# buck_converters_v1_1.net
KiCad netlist of a schematic drawn in EAGLE
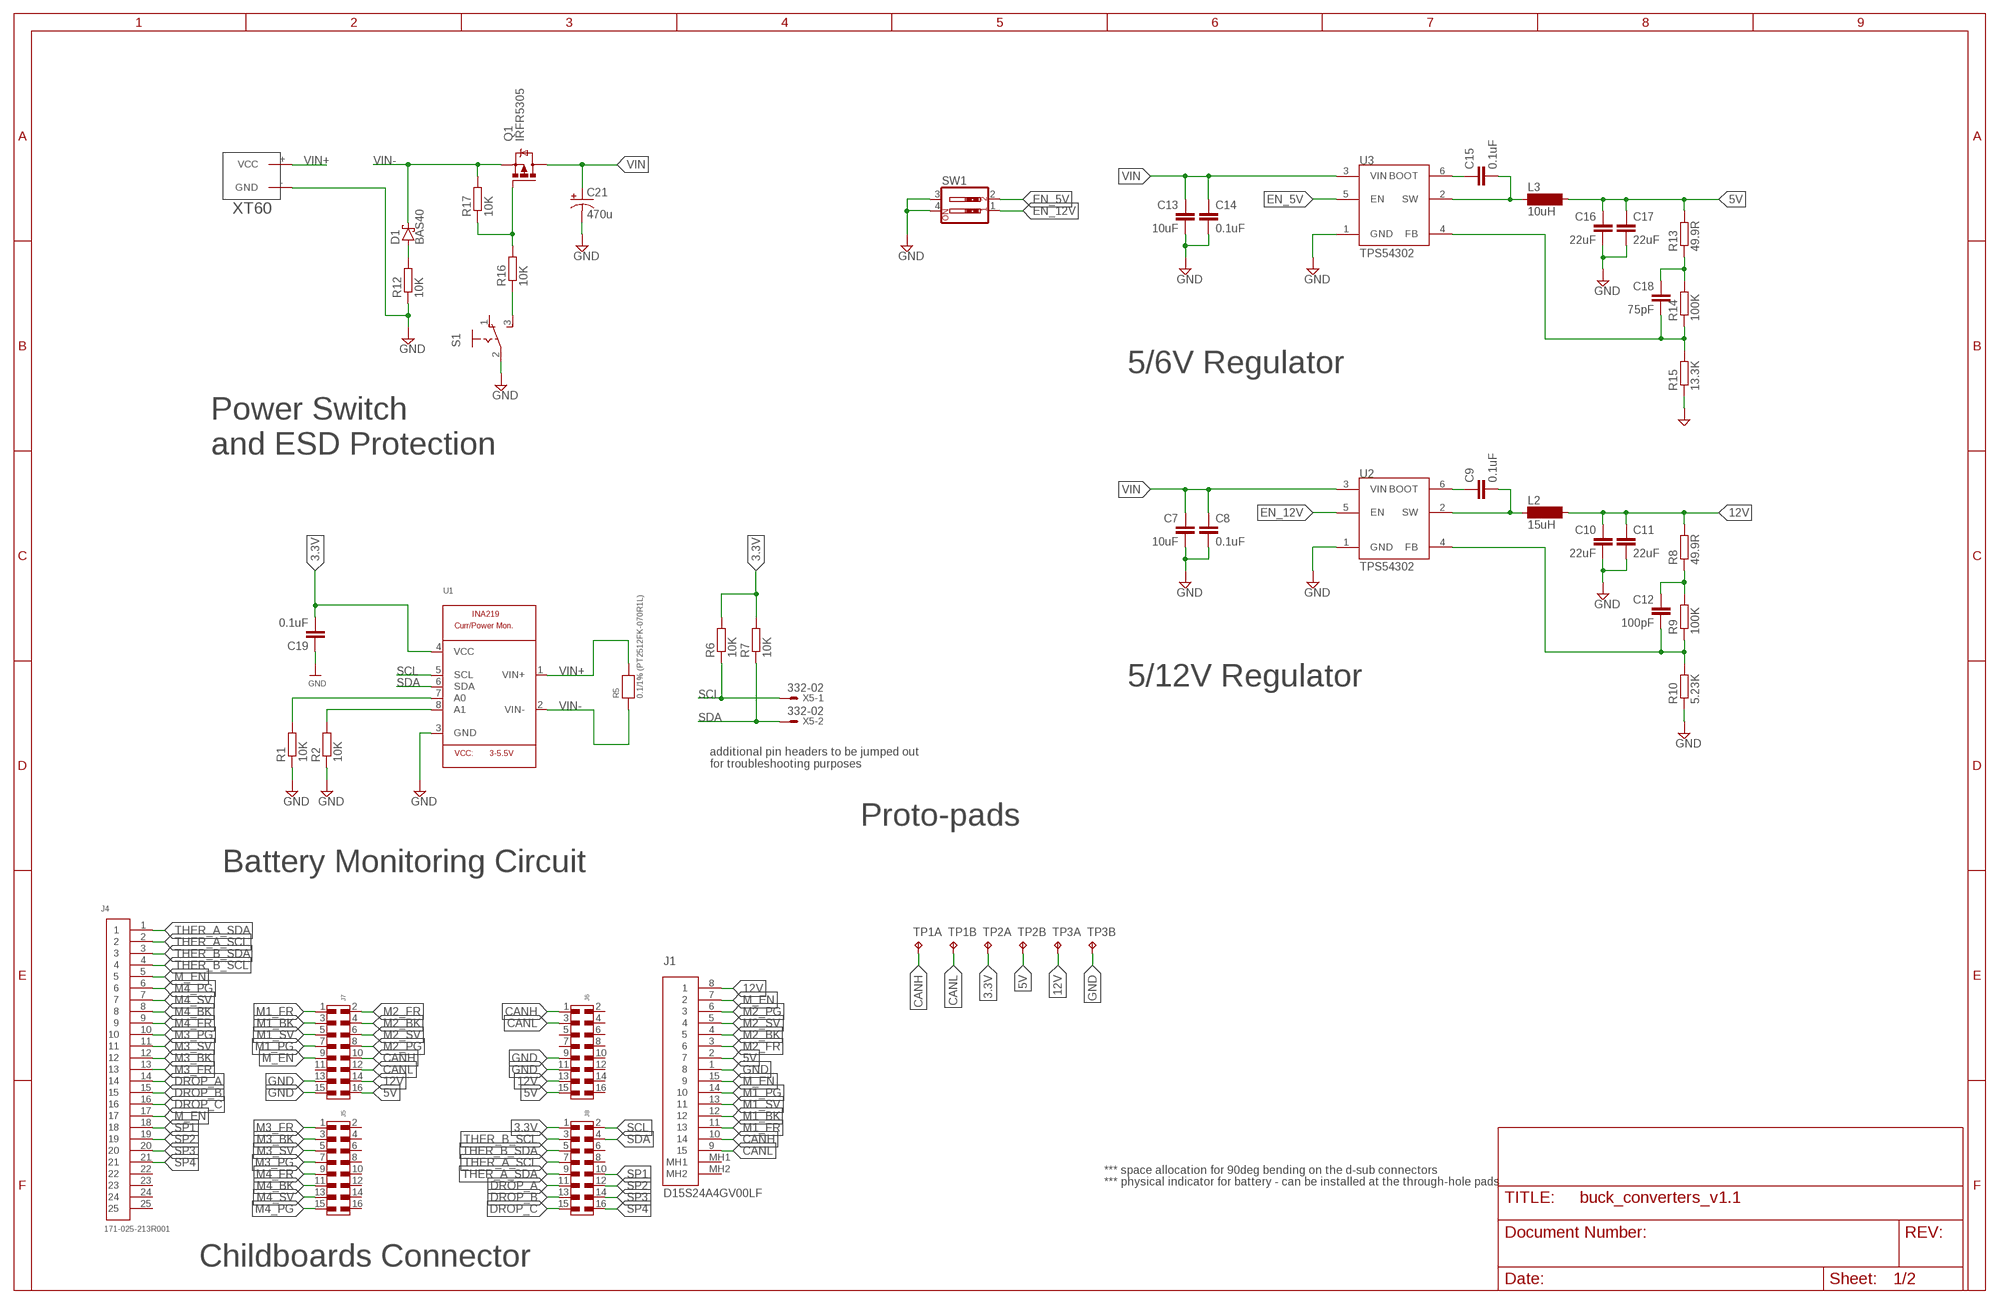
[diagram p0: schematic, sheet 1]
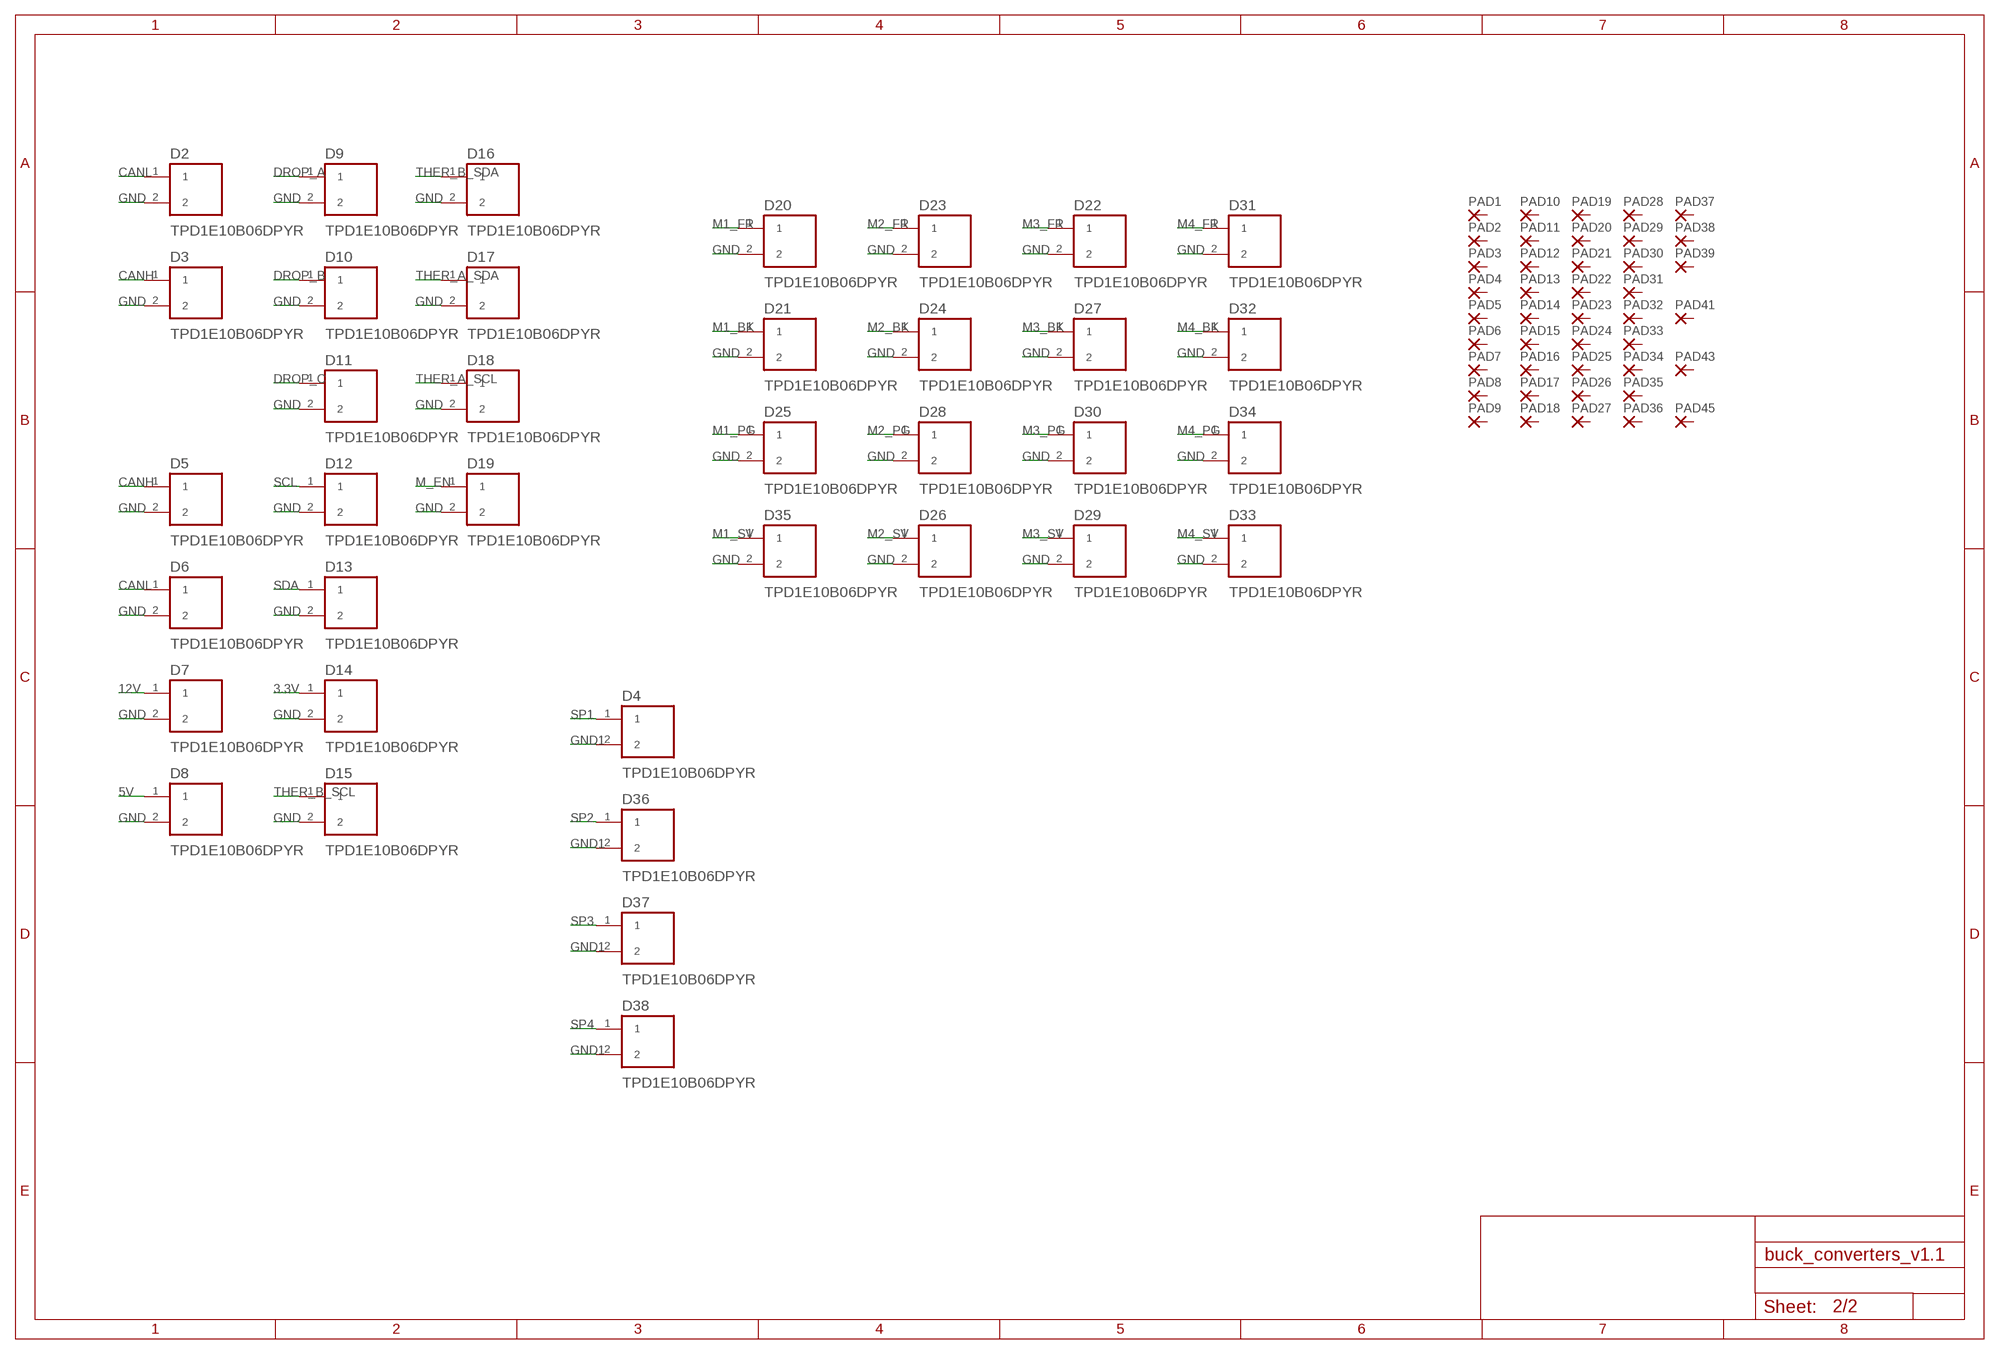
[diagram p1: schematic, sheet 2]

(export (version "E")
  (design (tool "Eeschema 10.0.6"))
  (components
    (comp (ref "C7")
      (value "10uF")
      (footprint "eagle-import:C0805")
      (libsource (lib "eagle-import") (part "C-EUC0805"))
    )
    (comp (ref "C8")
      (value "0.1uF")
      (footprint "eagle-import:C0805")
      (libsource (lib "eagle-import") (part "C-EUC0805"))
    )
    (comp (ref "C9")
      (value "0.1uF")
      (footprint "eagle-import:C0805")
      (libsource (lib "eagle-import") (part "C-EUC0805"))
    )
    (comp (ref "C10")
      (value "22uF")
      (footprint "eagle-import:C0805")
      (libsource (lib "eagle-import") (part "C-EUC0805"))
    )
    (comp (ref "C11")
      (value "22uF")
      (footprint "eagle-import:C0805")
      (libsource (lib "eagle-import") (part "C-EUC0805"))
    )
    (comp (ref "C12")
      (value "100pF")
      (footprint "eagle-import:C0805")
      (libsource (lib "eagle-import") (part "C-EUC0805"))
    )
    (comp (ref "C13")
      (value "10uF")
      (footprint "eagle-import:C0805")
      (libsource (lib "eagle-import") (part "C-EUC0805"))
    )
    (comp (ref "C14")
      (value "0.1uF")
      (footprint "eagle-import:C0805")
      (libsource (lib "eagle-import") (part "C-EUC0805"))
    )
    (comp (ref "C15")
      (value "0.1uF")
      (footprint "eagle-import:C0805")
      (libsource (lib "eagle-import") (part "C-EUC0805"))
    )
    (comp (ref "C16")
      (value "22uF")
      (footprint "eagle-import:C0805")
      (libsource (lib "eagle-import") (part "C-EUC0805"))
    )
    (comp (ref "C17")
      (value "22uF")
      (footprint "eagle-import:C0805")
      (libsource (lib "eagle-import") (part "C-EUC0805"))
    )
    (comp (ref "C18")
      (value "75pF")
      (footprint "eagle-import:C0805")
      (libsource (lib "eagle-import") (part "C-EUC0805"))
    )
    (comp (ref "C19")
      (value "0.1uF")
      (footprint "eagle-import:C0805")
      (libsource (lib "eagle-import") (part "C-EUC0805"))
    )
    (comp (ref "C21")
      (value "470u")
      (footprint "eagle-import:153CLV-1010")
      (libsource (lib "eagle-import") (part "CPOL-US153CLV-1010"))
    )
    (comp (ref "D1")
      (value "BAS40")
      (footprint "eagle-import:SOT23")
      (libsource (lib "eagle-import") (part "BAS40"))
    )
    (comp (ref "J1")
      (value "D15S24A4GV00LF")
      (footprint "eagle-import:D15S24A4GV00LF")
      (fields
        (field (name "DIGIKEY_PART_NUMBER") "609-1497-ND")
        (field (name "MANUFACTURER") "Amphenol ICC (FCI)")
        (field (name "CREATED_BY") "PCBLayout.com")
      )
      (libsource (lib "eagle-import") (part "D15S24A4GV00LF"))
    )
    (comp (ref "J4")
      (value "171-025-213R001")
      (footprint "eagle-import:171-025-213R001")
      (fields
        (field (name "DIGIKEY_PART_NO") "4225FE-ND")
        (field (name "MANUFACTURER") "NorComp Inc.")
        (field (name "CREATED_BY") "PCBLayout.com")
      )
      (libsource (lib "eagle-import") (part "171-025-213R001"))
    )
    (comp (ref "J5")
      (value "6120XX20621_61201620621")
      (footprint "eagle-import:61201620621")
      (libsource (lib "eagle-import") (part "6120XX20621_61201620621"))
    )
    (comp (ref "J6")
      (value "6120XX20621_61201620621")
      (footprint "eagle-import:61201620621")
      (libsource (lib "eagle-import") (part "6120XX20621_61201620621"))
    )
    (comp (ref "J7")
      (value "6123XX20621_61231620621")
      (footprint "eagle-import:61231620621")
      (libsource (lib "eagle-import") (part "6123XX20621_61231620621"))
    )
    (comp (ref "J8")
      (value "6120XX20621_61201620621")
      (footprint "eagle-import:61201620621")
      (libsource (lib "eagle-import") (part "6120XX20621_61201620621"))
    )
    (comp (ref "L2")
      (value "15uH")
      (footprint "eagle-import:SM-NE29")
      (libsource (lib "eagle-import") (part "SM-NE29"))
    )
    (comp (ref "L3")
      (value "10uH")
      (footprint "eagle-import:SM-NE29")
      (libsource (lib "eagle-import") (part "SM-NE29"))
    )
    (comp (ref "Q1")
      (value "IRFR5305")
      (footprint "eagle-import:D-PAK_TO252AA")
      (libsource (lib "eagle-import") (part "IRF?5305R"))
    )
    (comp (ref "R1")
      (value "10K")
      (footprint "eagle-import:R0805")
      (libsource (lib "eagle-import") (part "R-EU_R0805"))
    )
    (comp (ref "R2")
      (value "10K")
      (footprint "eagle-import:R0805")
      (libsource (lib "eagle-import") (part "R-EU_R0805"))
    )
    (comp (ref "R5")
      (value "0.1/1% (PT2512FK-070R1L)")
      (footprint "eagle-import:2512")
      (libsource (lib "eagle-import") (part "RESISTOR2512"))
    )
    (comp (ref "R6")
      (value "10K")
      (footprint "eagle-import:R0805")
      (libsource (lib "eagle-import") (part "R-EU_R0805"))
    )
    (comp (ref "R7")
      (value "10K")
      (footprint "eagle-import:R0805")
      (libsource (lib "eagle-import") (part "R-EU_R0805"))
    )
    (comp (ref "R8")
      (value "49.9R")
      (footprint "eagle-import:R0805")
      (libsource (lib "eagle-import") (part "R-EU_R0805"))
    )
    (comp (ref "R9")
      (value "100K")
      (footprint "eagle-import:R0805")
      (libsource (lib "eagle-import") (part "R-EU_R0805"))
    )
    (comp (ref "R10")
      (value "5.23K")
      (footprint "eagle-import:R0805")
      (libsource (lib "eagle-import") (part "R-EU_R0805"))
    )
    (comp (ref "R12")
      (value "10K")
      (footprint "eagle-import:R0805")
      (libsource (lib "eagle-import") (part "R-EU_R0805"))
    )
    (comp (ref "R13")
      (value "49.9R")
      (footprint "eagle-import:R0805")
      (libsource (lib "eagle-import") (part "R-EU_R0805"))
    )
    (comp (ref "R14")
      (value "100K")
      (footprint "eagle-import:R0805")
      (libsource (lib "eagle-import") (part "R-EU_R0805"))
    )
    (comp (ref "R15")
      (value "13.3K")
      (footprint "eagle-import:R0805")
      (libsource (lib "eagle-import") (part "R-EU_R0805"))
    )
    (comp (ref "R16")
      (value "10K")
      (footprint "eagle-import:R0805")
      (libsource (lib "eagle-import") (part "R-EU_R0805"))
    )
    (comp (ref "R17")
      (value "10K")
      (footprint "eagle-import:R0805")
      (libsource (lib "eagle-import") (part "R-EU_R0805"))
    )
    (comp (ref "S1")
      (value "255SB")
      (footprint "eagle-import:255SB")
      (libsource (lib "eagle-import") (part "255SB"))
    )
    (comp (ref "SW1")
      (value "SW_DIP-2")
      (footprint "eagle-import:EDG-02")
      (libsource (lib "eagle-import") (part "SW_DIP-2"))
    )
    (comp (ref "TP1")
      (value "TP2P2-38-17")
      (footprint "eagle-import:P2-38-17")
      (libsource (lib "eagle-import") (part "TP2P2-38-17"))
    )
    (comp (ref "TP2")
      (value "TP2P2-38-17")
      (footprint "eagle-import:P2-38-17")
      (libsource (lib "eagle-import") (part "TP2P2-38-17"))
    )
    (comp (ref "TP3")
      (value "TP2P2-38-17")
      (footprint "eagle-import:P2-38-17")
      (libsource (lib "eagle-import") (part "TP2P2-38-17"))
    )
    (comp (ref "U$9")
      (value "XT60")
      (footprint "eagle-import:XT60")
      (libsource (lib "eagle-import") (part "XT60"))
    )
    (comp (ref "U1")
      (value "INA219")
      (footprint "eagle-import:SOT23-8")
      (libsource (lib "eagle-import") (part "INA219"))
    )
    (comp (ref "U2")
      (value "TPS54302")
      (footprint "eagle-import:SOT23-6")
      (libsource (lib "eagle-import") (part "TPS54302"))
    )
    (comp (ref "U3")
      (value "TPS54302")
      (footprint "eagle-import:SOT23-6")
      (libsource (lib "eagle-import") (part "TPS54302"))
    )
    (comp (ref "X5")
      (value "332-02")
      (footprint "eagle-import:332-02")
      (libsource (lib "eagle-import") (part "332-02"))
    )
    (comp (ref "D2")
      (value "TPD1E10B06DPYR")
      (footprint "eagle-import:DIO_TPD1E05U06DPYR")
      (fields (field (name "MF") "Texas Instruments"))
      (libsource (lib "eagle-import") (part "TPD1E10B06DPYR"))
    )
    (comp (ref "D3")
      (value "TPD1E10B06DPYR")
      (footprint "eagle-import:DIO_TPD1E05U06DPYR")
      (fields (field (name "MF") "Texas Instruments"))
      (libsource (lib "eagle-import") (part "TPD1E10B06DPYR"))
    )
    (comp (ref "D4")
      (value "TPD1E10B06DPYR")
      (footprint "eagle-import:DIO_TPD1E05U06DPYR")
      (fields (field (name "MF") "Texas Instruments"))
      (libsource (lib "eagle-import") (part "TPD1E10B06DPYR"))
    )
    (comp (ref "D5")
      (value "TPD1E10B06DPYR")
      (footprint "eagle-import:DIO_TPD1E05U06DPYR")
      (fields (field (name "MF") "Texas Instruments"))
      (libsource (lib "eagle-import") (part "TPD1E10B06DPYR"))
    )
    (comp (ref "D6")
      (value "TPD1E10B06DPYR")
      (footprint "eagle-import:DIO_TPD1E05U06DPYR")
      (fields (field (name "MF") "Texas Instruments"))
      (libsource (lib "eagle-import") (part "TPD1E10B06DPYR"))
    )
    (comp (ref "D7")
      (value "TPD1E10B06DPYR")
      (footprint "eagle-import:DIO_TPD1E05U06DPYR")
      (fields (field (name "MF") "Texas Instruments"))
      (libsource (lib "eagle-import") (part "TPD1E10B06DPYR"))
    )
    (comp (ref "D8")
      (value "TPD1E10B06DPYR")
      (footprint "eagle-import:DIO_TPD1E05U06DPYR")
      (fields (field (name "MF") "Texas Instruments"))
      (libsource (lib "eagle-import") (part "TPD1E10B06DPYR"))
    )
    (comp (ref "D9")
      (value "TPD1E10B06DPYR")
      (footprint "eagle-import:DIO_TPD1E05U06DPYR")
      (fields (field (name "MF") "Texas Instruments"))
      (libsource (lib "eagle-import") (part "TPD1E10B06DPYR"))
    )
    (comp (ref "D10")
      (value "TPD1E10B06DPYR")
      (footprint "eagle-import:DIO_TPD1E05U06DPYR")
      (fields (field (name "MF") "Texas Instruments"))
      (libsource (lib "eagle-import") (part "TPD1E10B06DPYR"))
    )
    (comp (ref "D11")
      (value "TPD1E10B06DPYR")
      (footprint "eagle-import:DIO_TPD1E05U06DPYR")
      (fields (field (name "MF") "Texas Instruments"))
      (libsource (lib "eagle-import") (part "TPD1E10B06DPYR"))
    )
    (comp (ref "D12")
      (value "TPD1E10B06DPYR")
      (footprint "eagle-import:DIO_TPD1E05U06DPYR")
      (fields (field (name "MF") "Texas Instruments"))
      (libsource (lib "eagle-import") (part "TPD1E10B06DPYR"))
    )
    (comp (ref "D13")
      (value "TPD1E10B06DPYR")
      (footprint "eagle-import:DIO_TPD1E05U06DPYR")
      (fields (field (name "MF") "Texas Instruments"))
      (libsource (lib "eagle-import") (part "TPD1E10B06DPYR"))
    )
    (comp (ref "D14")
      (value "TPD1E10B06DPYR")
      (footprint "eagle-import:DIO_TPD1E05U06DPYR")
      (fields (field (name "MF") "Texas Instruments"))
      (libsource (lib "eagle-import") (part "TPD1E10B06DPYR"))
    )
    (comp (ref "D15")
      (value "TPD1E10B06DPYR")
      (footprint "eagle-import:DIO_TPD1E05U06DPYR")
      (fields (field (name "MF") "Texas Instruments"))
      (libsource (lib "eagle-import") (part "TPD1E10B06DPYR"))
    )
    (comp (ref "D16")
      (value "TPD1E10B06DPYR")
      (footprint "eagle-import:DIO_TPD1E05U06DPYR")
      (fields (field (name "MF") "Texas Instruments"))
      (libsource (lib "eagle-import") (part "TPD1E10B06DPYR"))
    )
    (comp (ref "D17")
      (value "TPD1E10B06DPYR")
      (footprint "eagle-import:DIO_TPD1E05U06DPYR")
      (fields (field (name "MF") "Texas Instruments"))
      (libsource (lib "eagle-import") (part "TPD1E10B06DPYR"))
    )
    (comp (ref "D18")
      (value "TPD1E10B06DPYR")
      (footprint "eagle-import:DIO_TPD1E05U06DPYR")
      (fields (field (name "MF") "Texas Instruments"))
      (libsource (lib "eagle-import") (part "TPD1E10B06DPYR"))
    )
    (comp (ref "D19")
      (value "TPD1E10B06DPYR")
      (footprint "eagle-import:DIO_TPD1E05U06DPYR")
      (fields (field (name "MF") "Texas Instruments"))
      (libsource (lib "eagle-import") (part "TPD1E10B06DPYR"))
    )
    (comp (ref "D20")
      (value "TPD1E10B06DPYR")
      (footprint "eagle-import:DIO_TPD1E05U06DPYR")
      (fields (field (name "MF") "Texas Instruments"))
      (libsource (lib "eagle-import") (part "TPD1E10B06DPYR"))
    )
    (comp (ref "D21")
      (value "TPD1E10B06DPYR")
      (footprint "eagle-import:DIO_TPD1E05U06DPYR")
      (fields (field (name "MF") "Texas Instruments"))
      (libsource (lib "eagle-import") (part "TPD1E10B06DPYR"))
    )
    (comp (ref "D22")
      (value "TPD1E10B06DPYR")
      (footprint "eagle-import:DIO_TPD1E05U06DPYR")
      (fields (field (name "MF") "Texas Instruments"))
      (libsource (lib "eagle-import") (part "TPD1E10B06DPYR"))
    )
    (comp (ref "D23")
      (value "TPD1E10B06DPYR")
      (footprint "eagle-import:DIO_TPD1E05U06DPYR")
      (fields (field (name "MF") "Texas Instruments"))
      (libsource (lib "eagle-import") (part "TPD1E10B06DPYR"))
    )
    (comp (ref "D24")
      (value "TPD1E10B06DPYR")
      (footprint "eagle-import:DIO_TPD1E05U06DPYR")
      (fields (field (name "MF") "Texas Instruments"))
      (libsource (lib "eagle-import") (part "TPD1E10B06DPYR"))
    )
    (comp (ref "D25")
      (value "TPD1E10B06DPYR")
      (footprint "eagle-import:DIO_TPD1E05U06DPYR")
      (fields (field (name "MF") "Texas Instruments"))
      (libsource (lib "eagle-import") (part "TPD1E10B06DPYR"))
    )
    (comp (ref "D26")
      (value "TPD1E10B06DPYR")
      (footprint "eagle-import:DIO_TPD1E05U06DPYR")
      (fields (field (name "MF") "Texas Instruments"))
      (libsource (lib "eagle-import") (part "TPD1E10B06DPYR"))
    )
    (comp (ref "D27")
      (value "TPD1E10B06DPYR")
      (footprint "eagle-import:DIO_TPD1E05U06DPYR")
      (fields (field (name "MF") "Texas Instruments"))
      (libsource (lib "eagle-import") (part "TPD1E10B06DPYR"))
    )
    (comp (ref "D28")
      (value "TPD1E10B06DPYR")
      (footprint "eagle-import:DIO_TPD1E05U06DPYR")
      (fields (field (name "MF") "Texas Instruments"))
      (libsource (lib "eagle-import") (part "TPD1E10B06DPYR"))
    )
    (comp (ref "D29")
      (value "TPD1E10B06DPYR")
      (footprint "eagle-import:DIO_TPD1E05U06DPYR")
      (fields (field (name "MF") "Texas Instruments"))
      (libsource (lib "eagle-import") (part "TPD1E10B06DPYR"))
    )
    (comp (ref "D30")
      (value "TPD1E10B06DPYR")
      (footprint "eagle-import:DIO_TPD1E05U06DPYR")
      (fields (field (name "MF") "Texas Instruments"))
      (libsource (lib "eagle-import") (part "TPD1E10B06DPYR"))
    )
    (comp (ref "D31")
      (value "TPD1E10B06DPYR")
      (footprint "eagle-import:DIO_TPD1E05U06DPYR")
      (fields (field (name "MF") "Texas Instruments"))
      (libsource (lib "eagle-import") (part "TPD1E10B06DPYR"))
    )
    (comp (ref "D32")
      (value "TPD1E10B06DPYR")
      (footprint "eagle-import:DIO_TPD1E05U06DPYR")
      (fields (field (name "MF") "Texas Instruments"))
      (libsource (lib "eagle-import") (part "TPD1E10B06DPYR"))
    )
    (comp (ref "D33")
      (value "TPD1E10B06DPYR")
      (footprint "eagle-import:DIO_TPD1E05U06DPYR")
      (fields (field (name "MF") "Texas Instruments"))
      (libsource (lib "eagle-import") (part "TPD1E10B06DPYR"))
    )
    (comp (ref "D34")
      (value "TPD1E10B06DPYR")
      (footprint "eagle-import:DIO_TPD1E05U06DPYR")
      (fields (field (name "MF") "Texas Instruments"))
      (libsource (lib "eagle-import") (part "TPD1E10B06DPYR"))
    )
    (comp (ref "D35")
      (value "TPD1E10B06DPYR")
      (footprint "eagle-import:DIO_TPD1E05U06DPYR")
      (fields (field (name "MF") "Texas Instruments"))
      (libsource (lib "eagle-import") (part "TPD1E10B06DPYR"))
    )
    (comp (ref "D36")
      (value "TPD1E10B06DPYR")
      (footprint "eagle-import:DIO_TPD1E05U06DPYR")
      (fields (field (name "MF") "Texas Instruments"))
      (libsource (lib "eagle-import") (part "TPD1E10B06DPYR"))
    )
    (comp (ref "D37")
      (value "TPD1E10B06DPYR")
      (footprint "eagle-import:DIO_TPD1E05U06DPYR")
      (fields (field (name "MF") "Texas Instruments"))
      (libsource (lib "eagle-import") (part "TPD1E10B06DPYR"))
    )
    (comp (ref "D38")
      (value "TPD1E10B06DPYR")
      (footprint "eagle-import:DIO_TPD1E05U06DPYR")
      (fields (field (name "MF") "Texas Instruments"))
      (libsource (lib "eagle-import") (part "TPD1E10B06DPYR"))
    )
    (comp (ref "PAD1")
      (value "2,54/1,1")
      (footprint "eagle-import:2,54_1,1")
      (libsource (lib "eagle-import") (part "2,54/1,1"))
    )
    (comp (ref "PAD2")
      (value "2,54/1,1")
      (footprint "eagle-import:2,54_1,1")
      (libsource (lib "eagle-import") (part "2,54/1,1"))
    )
    (comp (ref "PAD3")
      (value "2,54/1,1")
      (footprint "eagle-import:2,54_1,1")
      (libsource (lib "eagle-import") (part "2,54/1,1"))
    )
    (comp (ref "PAD4")
      (value "2,54/1,1")
      (footprint "eagle-import:2,54_1,1")
      (libsource (lib "eagle-import") (part "2,54/1,1"))
    )
    (comp (ref "PAD5")
      (value "2,54/1,1")
      (footprint "eagle-import:2,54_1,1")
      (libsource (lib "eagle-import") (part "2,54/1,1"))
    )
    (comp (ref "PAD6")
      (value "2,54/1,1")
      (footprint "eagle-import:2,54_1,1")
      (libsource (lib "eagle-import") (part "2,54/1,1"))
    )
    (comp (ref "PAD7")
      (value "2,54/1,1")
      (footprint "eagle-import:2,54_1,1")
      (libsource (lib "eagle-import") (part "2,54/1,1"))
    )
    (comp (ref "PAD8")
      (value "2,54/1,1")
      (footprint "eagle-import:2,54_1,1")
      (libsource (lib "eagle-import") (part "2,54/1,1"))
    )
    (comp (ref "PAD9")
      (value "2,54/1,1")
      (footprint "eagle-import:2,54_1,1")
      (libsource (lib "eagle-import") (part "2,54/1,1"))
    )
    (comp (ref "PAD10")
      (value "2,54/1,1")
      (footprint "eagle-import:2,54_1,1")
      (libsource (lib "eagle-import") (part "2,54/1,1"))
    )
    (comp (ref "PAD11")
      (value "2,54/1,1")
      (footprint "eagle-import:2,54_1,1")
      (libsource (lib "eagle-import") (part "2,54/1,1"))
    )
    (comp (ref "PAD12")
      (value "2,54/1,1")
      (footprint "eagle-import:2,54_1,1")
      (libsource (lib "eagle-import") (part "2,54/1,1"))
    )
    (comp (ref "PAD13")
      (value "2,54/1,1")
      (footprint "eagle-import:2,54_1,1")
      (libsource (lib "eagle-import") (part "2,54/1,1"))
    )
    (comp (ref "PAD14")
      (value "2,54/1,1")
      (footprint "eagle-import:2,54_1,1")
      (libsource (lib "eagle-import") (part "2,54/1,1"))
    )
    (comp (ref "PAD15")
      (value "2,54/1,1")
      (footprint "eagle-import:2,54_1,1")
      (libsource (lib "eagle-import") (part "2,54/1,1"))
    )
    (comp (ref "PAD16")
      (value "2,54/1,1")
      (footprint "eagle-import:2,54_1,1")
      (libsource (lib "eagle-import") (part "2,54/1,1"))
    )
    (comp (ref "PAD17")
      (value "2,54/1,1")
      (footprint "eagle-import:2,54_1,1")
      (libsource (lib "eagle-import") (part "2,54/1,1"))
    )
    (comp (ref "PAD18")
      (value "2,54/1,1")
      (footprint "eagle-import:2,54_1,1")
      (libsource (lib "eagle-import") (part "2,54/1,1"))
    )
    (comp (ref "PAD19")
      (value "2,54/1,1")
      (footprint "eagle-import:2,54_1,1")
      (libsource (lib "eagle-import") (part "2,54/1,1"))
    )
    (comp (ref "PAD20")
      (value "2,54/1,1")
      (footprint "eagle-import:2,54_1,1")
      (libsource (lib "eagle-import") (part "2,54/1,1"))
    )
    (comp (ref "PAD21")
      (value "2,54/1,1")
      (footprint "eagle-import:2,54_1,1")
      (libsource (lib "eagle-import") (part "2,54/1,1"))
    )
    (comp (ref "PAD22")
      (value "2,54/1,1")
      (footprint "eagle-import:2,54_1,1")
      (libsource (lib "eagle-import") (part "2,54/1,1"))
    )
    (comp (ref "PAD23")
      (value "2,54/1,1")
      (footprint "eagle-import:2,54_1,1")
      (libsource (lib "eagle-import") (part "2,54/1,1"))
    )
    (comp (ref "PAD24")
      (value "2,54/1,1")
      (footprint "eagle-import:2,54_1,1")
      (libsource (lib "eagle-import") (part "2,54/1,1"))
    )
    (comp (ref "PAD25")
      (value "2,54/1,1")
      (footprint "eagle-import:2,54_1,1")
      (libsource (lib "eagle-import") (part "2,54/1,1"))
    )
    (comp (ref "PAD26")
      (value "2,54/1,1")
      (footprint "eagle-import:2,54_1,1")
      (libsource (lib "eagle-import") (part "2,54/1,1"))
    )
    (comp (ref "PAD27")
      (value "2,54/1,1")
      (footprint "eagle-import:2,54_1,1")
      (libsource (lib "eagle-import") (part "2,54/1,1"))
    )
    (comp (ref "PAD28")
      (value "2,54/1,1")
      (footprint "eagle-import:2,54_1,1")
      (libsource (lib "eagle-import") (part "2,54/1,1"))
    )
    (comp (ref "PAD29")
      (value "2,54/1,1")
      (footprint "eagle-import:2,54_1,1")
      (libsource (lib "eagle-import") (part "2,54/1,1"))
    )
    (comp (ref "PAD30")
      (value "2,54/1,1")
      (footprint "eagle-import:2,54_1,1")
      (libsource (lib "eagle-import") (part "2,54/1,1"))
    )
    (comp (ref "PAD31")
      (value "2,54/1,1")
      (footprint "eagle-import:2,54_1,1")
      (libsource (lib "eagle-import") (part "2,54/1,1"))
    )
    (comp (ref "PAD32")
      (value "2,54/1,1")
      (footprint "eagle-import:2,54_1,1")
      (libsource (lib "eagle-import") (part "2,54/1,1"))
    )
    (comp (ref "PAD33")
      (value "2,54/1,1")
      (footprint "eagle-import:2,54_1,1")
      (libsource (lib "eagle-import") (part "2,54/1,1"))
    )
    (comp (ref "PAD34")
      (value "2,54/1,1")
      (footprint "eagle-import:2,54_1,1")
      (libsource (lib "eagle-import") (part "2,54/1,1"))
    )
    (comp (ref "PAD35")
      (value "2,54/1,1")
      (footprint "eagle-import:2,54_1,1")
      (libsource (lib "eagle-import") (part "2,54/1,1"))
    )
    (comp (ref "PAD36")
      (value "2,54/1,1")
      (footprint "eagle-import:2,54_1,1")
      (libsource (lib "eagle-import") (part "2,54/1,1"))
    )
    (comp (ref "PAD37")
      (value "2,54/1,1")
      (footprint "eagle-import:2,54_1,1")
      (libsource (lib "eagle-import") (part "2,54/1,1"))
    )
    (comp (ref "PAD38")
      (value "2,54/1,1")
      (footprint "eagle-import:2,54_1,1")
      (libsource (lib "eagle-import") (part "2,54/1,1"))
    )
    (comp (ref "PAD39")
      (value "2,54/1,1")
      (footprint "eagle-import:2,54_1,1")
      (libsource (lib "eagle-import") (part "2,54/1,1"))
    )
    (comp (ref "PAD41")
      (value "2,54/1,1")
      (footprint "eagle-import:2,54_1,1")
      (libsource (lib "eagle-import") (part "2,54/1,1"))
    )
    (comp (ref "PAD43")
      (value "2,54/1,1")
      (footprint "eagle-import:2,54_1,1")
      (libsource (lib "eagle-import") (part "2,54/1,1"))
    )
    (comp (ref "PAD45")
      (value "2,54/1,1")
      (footprint "eagle-import:2,54_1,1")
      (libsource (lib "eagle-import") (part "2,54/1,1"))
    )
  )
  (nets
    (net (code "1") (name "3.3V") (class "Default")
      (node (ref "C19") (pin "2") (pinfunction "2_2") (pintype "passive"))
      (node (ref "D14") (pin "1") (pinfunction "1_1") (pintype "bidirectional"))
      (node (ref "J8") (pin "1") (pinfunction "1_1") (pintype "passive"))
      (node (ref "R6") (pin "2") (pinfunction "2_2") (pintype "passive"))
      (node (ref "R7") (pin "2") (pinfunction "2_2") (pintype "passive"))
      (node (ref "TP2") (pin "TP-1") (pinfunction "TP_TP-1") (pintype "input"))
      (node (ref "U1") (pin "4") (pinfunction "VCC_4") (pintype "bidirectional"))
    )
    (net (code "2") (name "5V") (class "Default")
      (node (ref "C16") (pin "1") (pinfunction "1_1") (pintype "passive"))
      (node (ref "C17") (pin "1") (pinfunction "1_1") (pintype "passive"))
      (node (ref "D8") (pin "1") (pinfunction "1_1") (pintype "bidirectional"))
      (node (ref "J1") (pin "2") (pinfunction "7_2") (pintype "passive"))
      (node (ref "J6") (pin "15") (pinfunction "15_15") (pintype "passive"))
      (node (ref "J7") (pin "16") (pinfunction "16_16") (pintype "passive"))
      (node (ref "L3") (pin "2") (pinfunction "2_2") (pintype "passive"))
      (node (ref "R13") (pin "2") (pinfunction "2_2") (pintype "passive"))
      (node (ref "TP2") (pin "TP-2") (pinfunction "TP_TP-2") (pintype "input"))
    )
    (net (code "3") (name "12V") (class "Default")
      (node (ref "C10") (pin "1") (pinfunction "1_1") (pintype "passive"))
      (node (ref "C11") (pin "1") (pinfunction "1_1") (pintype "passive"))
      (node (ref "D7") (pin "1") (pinfunction "1_1") (pintype "bidirectional"))
      (node (ref "J1") (pin "8") (pinfunction "1_8") (pintype "passive"))
      (node (ref "J6") (pin "13") (pinfunction "13_13") (pintype "passive"))
      (node (ref "J7") (pin "14") (pinfunction "14_14") (pintype "passive"))
      (node (ref "L2") (pin "2") (pinfunction "2_2") (pintype "passive"))
      (node (ref "R8") (pin "2") (pinfunction "2_2") (pintype "passive"))
      (node (ref "TP3") (pin "TP-1") (pinfunction "TP_TP-1") (pintype "input"))
    )
    (net (code "4") (name "CANH") (class "Default")
      (node (ref "D3") (pin "1") (pinfunction "1_1") (pintype "bidirectional"))
      (node (ref "D5") (pin "1") (pinfunction "1_1") (pintype "bidirectional"))
      (node (ref "J1") (pin "10") (pinfunction "14_10") (pintype "passive"))
      (node (ref "J6") (pin "1") (pinfunction "1_1") (pintype "passive"))
      (node (ref "J7") (pin "10") (pinfunction "10_10") (pintype "passive"))
      (node (ref "TP1") (pin "TP-1") (pinfunction "TP_TP-1") (pintype "input"))
    )
    (net (code "5") (name "CANL") (class "Default")
      (node (ref "D2") (pin "1") (pinfunction "1_1") (pintype "bidirectional"))
      (node (ref "D6") (pin "1") (pinfunction "1_1") (pintype "bidirectional"))
      (node (ref "J1") (pin "9") (pinfunction "15_9") (pintype "passive"))
      (node (ref "J6") (pin "3") (pinfunction "3_3") (pintype "passive"))
      (node (ref "J7") (pin "12") (pinfunction "12_12") (pintype "passive"))
      (node (ref "TP1") (pin "TP-2") (pinfunction "TP_TP-2") (pintype "input"))
    )
    (net (code "6") (name "DROP_A") (class "Default")
      (node (ref "D9") (pin "1") (pinfunction "1_1") (pintype "bidirectional"))
      (node (ref "J4") (pin "14") (pinfunction "14_14") (pintype "passive"))
      (node (ref "J8") (pin "11") (pinfunction "11_11") (pintype "passive"))
    )
    (net (code "7") (name "DROP_B") (class "Default")
      (node (ref "D10") (pin "1") (pinfunction "1_1") (pintype "bidirectional"))
      (node (ref "J4") (pin "15") (pinfunction "15_15") (pintype "passive"))
      (node (ref "J8") (pin "13") (pinfunction "13_13") (pintype "passive"))
    )
    (net (code "8") (name "DROP_C") (class "Default")
      (node (ref "D11") (pin "1") (pinfunction "1_1") (pintype "bidirectional"))
      (node (ref "J4") (pin "16") (pinfunction "16_16") (pintype "passive"))
      (node (ref "J8") (pin "15") (pinfunction "15_15") (pintype "passive"))
    )
    (net (code "9") (name "EN_5V") (class "Default")
      (node (ref "SW1") (pin "2") (pinfunction "2_2") (pintype "passive"))
      (node (ref "U3") (pin "5") (pinfunction "EN_5") (pintype "bidirectional"))
    )
    (net (code "10") (name "EN_12V") (class "Default")
      (node (ref "SW1") (pin "1") (pinfunction "1_1") (pintype "passive"))
      (node (ref "U2") (pin "5") (pinfunction "EN_5") (pintype "bidirectional"))
    )
    (net (code "11") (name "GND") (class "Default")
      (node (ref "C10") (pin "2") (pinfunction "2_2") (pintype "passive"))
      (node (ref "C11") (pin "2") (pinfunction "2_2") (pintype "passive"))
      (node (ref "C13") (pin "2") (pinfunction "2_2") (pintype "passive"))
      (node (ref "C14") (pin "2") (pinfunction "2_2") (pintype "passive"))
      (node (ref "C16") (pin "2") (pinfunction "2_2") (pintype "passive"))
      (node (ref "C17") (pin "2") (pinfunction "2_2") (pintype "passive"))
      (node (ref "C19") (pin "1") (pinfunction "1_1") (pintype "passive"))
      (node (ref "C21") (pin "-") (pinfunction "-_-") (pintype "passive"))
      (node (ref "C7") (pin "2") (pinfunction "2_2") (pintype "passive"))
      (node (ref "C8") (pin "2") (pinfunction "2_2") (pintype "passive"))
      (node (ref "D10") (pin "2") (pinfunction "2_2") (pintype "bidirectional"))
      (node (ref "D11") (pin "2") (pinfunction "2_2") (pintype "bidirectional"))
      (node (ref "D12") (pin "2") (pinfunction "2_2") (pintype "bidirectional"))
      (node (ref "D13") (pin "2") (pinfunction "2_2") (pintype "bidirectional"))
      (node (ref "D14") (pin "2") (pinfunction "2_2") (pintype "bidirectional"))
      (node (ref "D15") (pin "2") (pinfunction "2_2") (pintype "bidirectional"))
      (node (ref "D16") (pin "2") (pinfunction "2_2") (pintype "bidirectional"))
      (node (ref "D17") (pin "2") (pinfunction "2_2") (pintype "bidirectional"))
      (node (ref "D18") (pin "2") (pinfunction "2_2") (pintype "bidirectional"))
      (node (ref "D19") (pin "2") (pinfunction "2_2") (pintype "bidirectional"))
      (node (ref "D2") (pin "2") (pinfunction "2_2") (pintype "bidirectional"))
      (node (ref "D20") (pin "2") (pinfunction "2_2") (pintype "bidirectional"))
      (node (ref "D21") (pin "2") (pinfunction "2_2") (pintype "bidirectional"))
      (node (ref "D22") (pin "2") (pinfunction "2_2") (pintype "bidirectional"))
      (node (ref "D23") (pin "2") (pinfunction "2_2") (pintype "bidirectional"))
      (node (ref "D24") (pin "2") (pinfunction "2_2") (pintype "bidirectional"))
      (node (ref "D25") (pin "2") (pinfunction "2_2") (pintype "bidirectional"))
      (node (ref "D26") (pin "2") (pinfunction "2_2") (pintype "bidirectional"))
      (node (ref "D27") (pin "2") (pinfunction "2_2") (pintype "bidirectional"))
      (node (ref "D28") (pin "2") (pinfunction "2_2") (pintype "bidirectional"))
      (node (ref "D29") (pin "2") (pinfunction "2_2") (pintype "bidirectional"))
      (node (ref "D3") (pin "2") (pinfunction "2_2") (pintype "bidirectional"))
      (node (ref "D30") (pin "2") (pinfunction "2_2") (pintype "bidirectional"))
      (node (ref "D31") (pin "2") (pinfunction "2_2") (pintype "bidirectional"))
      (node (ref "D32") (pin "2") (pinfunction "2_2") (pintype "bidirectional"))
      (node (ref "D33") (pin "2") (pinfunction "2_2") (pintype "bidirectional"))
      (node (ref "D34") (pin "2") (pinfunction "2_2") (pintype "bidirectional"))
      (node (ref "D35") (pin "2") (pinfunction "2_2") (pintype "bidirectional"))
      (node (ref "D5") (pin "2") (pinfunction "2_2") (pintype "bidirectional"))
      (node (ref "D6") (pin "2") (pinfunction "2_2") (pintype "bidirectional"))
      (node (ref "D7") (pin "2") (pinfunction "2_2") (pintype "bidirectional"))
      (node (ref "D8") (pin "2") (pinfunction "2_2") (pintype "bidirectional"))
      (node (ref "D9") (pin "2") (pinfunction "2_2") (pintype "bidirectional"))
      (node (ref "J1") (pin "1") (pinfunction "8_1") (pintype "passive"))
      (node (ref "J6") (pin "11") (pinfunction "11_11") (pintype "passive"))
      (node (ref "J6") (pin "9") (pinfunction "9_9") (pintype "passive"))
      (node (ref "J7") (pin "13") (pinfunction "13_13") (pintype "passive"))
      (node (ref "J7") (pin "15") (pinfunction "15_15") (pintype "passive"))
      (node (ref "R1") (pin "1") (pinfunction "1_1") (pintype "passive"))
      (node (ref "R10") (pin "1") (pinfunction "1_1") (pintype "passive"))
      (node (ref "R12") (pin "1") (pinfunction "1_1") (pintype "passive"))
      (node (ref "R15") (pin "1") (pinfunction "1_1") (pintype "passive"))
      (node (ref "R2") (pin "1") (pinfunction "1_1") (pintype "passive"))
      (node (ref "S1") (pin "2") (pinfunction "P_2") (pintype "passive"))
      (node (ref "SW1") (pin "3") (pinfunction "3_3") (pintype "passive"))
      (node (ref "SW1") (pin "4") (pinfunction "4_4") (pintype "passive"))
      (node (ref "TP3") (pin "TP-2") (pinfunction "TP_TP-2") (pintype "input"))
      (node (ref "U$9") (pin "-") (pinfunction "GND_-") (pintype "bidirectional"))
      (node (ref "U1") (pin "3") (pinfunction "GND_3") (pintype "bidirectional"))
      (node (ref "U2") (pin "1") (pinfunction "GND_1") (pintype "bidirectional"))
      (node (ref "U3") (pin "1") (pinfunction "GND_1") (pintype "bidirectional"))
    )
    (net (code "12") (name "GND1") (class "Default")
      (node (ref "D36") (pin "2") (pinfunction "2_2") (pintype "bidirectional"))
      (node (ref "D37") (pin "2") (pinfunction "2_2") (pintype "bidirectional"))
      (node (ref "D38") (pin "2") (pinfunction "2_2") (pintype "bidirectional"))
      (node (ref "D4") (pin "2") (pinfunction "2_2") (pintype "bidirectional"))
    )
    (net (code "13") (name "M1_BK") (class "Default")
      (node (ref "D21") (pin "1") (pinfunction "1_1") (pintype "bidirectional"))
      (node (ref "J1") (pin "12") (pinfunction "12_12") (pintype "passive"))
      (node (ref "J7") (pin "3") (pinfunction "3_3") (pintype "passive"))
    )
    (net (code "14") (name "M1_FR") (class "Default")
      (node (ref "D20") (pin "1") (pinfunction "1_1") (pintype "bidirectional"))
      (node (ref "J1") (pin "11") (pinfunction "13_11") (pintype "passive"))
      (node (ref "J7") (pin "1") (pinfunction "1_1") (pintype "passive"))
    )
    (net (code "15") (name "M1_PG") (class "Default")
      (node (ref "D25") (pin "1") (pinfunction "1_1") (pintype "bidirectional"))
      (node (ref "J1") (pin "14") (pinfunction "10_14") (pintype "passive"))
      (node (ref "J7") (pin "7") (pinfunction "7_7") (pintype "passive"))
    )
    (net (code "16") (name "M1_SV") (class "Default")
      (node (ref "D35") (pin "1") (pinfunction "1_1") (pintype "bidirectional"))
      (node (ref "J1") (pin "13") (pinfunction "11_13") (pintype "passive"))
      (node (ref "J7") (pin "5") (pinfunction "5_5") (pintype "passive"))
    )
    (net (code "17") (name "M2_BK") (class "Default")
      (node (ref "D24") (pin "1") (pinfunction "1_1") (pintype "bidirectional"))
      (node (ref "J1") (pin "4") (pinfunction "5_4") (pintype "passive"))
      (node (ref "J7") (pin "4") (pinfunction "4_4") (pintype "passive"))
    )
    (net (code "18") (name "M2_FR") (class "Default")
      (node (ref "D23") (pin "1") (pinfunction "1_1") (pintype "bidirectional"))
      (node (ref "J1") (pin "3") (pinfunction "6_3") (pintype "passive"))
      (node (ref "J7") (pin "2") (pinfunction "2_2") (pintype "passive"))
    )
    (net (code "19") (name "M2_PG") (class "Default")
      (node (ref "D28") (pin "1") (pinfunction "1_1") (pintype "bidirectional"))
      (node (ref "J1") (pin "6") (pinfunction "3_6") (pintype "passive"))
      (node (ref "J7") (pin "8") (pinfunction "8_8") (pintype "passive"))
    )
    (net (code "20") (name "M2_SV") (class "Default")
      (node (ref "D26") (pin "1") (pinfunction "1_1") (pintype "bidirectional"))
      (node (ref "J1") (pin "5") (pinfunction "4_5") (pintype "passive"))
      (node (ref "J7") (pin "6") (pinfunction "6_6") (pintype "passive"))
    )
    (net (code "21") (name "M3_BK") (class "Default")
      (node (ref "D27") (pin "1") (pinfunction "1_1") (pintype "bidirectional"))
      (node (ref "J4") (pin "12") (pinfunction "12_12") (pintype "passive"))
      (node (ref "J5") (pin "3") (pinfunction "3_3") (pintype "passive"))
    )
    (net (code "22") (name "M3_FR") (class "Default")
      (node (ref "D22") (pin "1") (pinfunction "1_1") (pintype "bidirectional"))
      (node (ref "J4") (pin "13") (pinfunction "13_13") (pintype "passive"))
      (node (ref "J5") (pin "1") (pinfunction "1_1") (pintype "passive"))
    )
    (net (code "23") (name "M3_PG") (class "Default")
      (node (ref "D30") (pin "1") (pinfunction "1_1") (pintype "bidirectional"))
      (node (ref "J4") (pin "10") (pinfunction "10_10") (pintype "passive"))
      (node (ref "J5") (pin "7") (pinfunction "7_7") (pintype "passive"))
    )
    (net (code "24") (name "M3_SV") (class "Default")
      (node (ref "D29") (pin "1") (pinfunction "1_1") (pintype "bidirectional"))
      (node (ref "J4") (pin "11") (pinfunction "11_11") (pintype "passive"))
      (node (ref "J5") (pin "5") (pinfunction "5_5") (pintype "passive"))
    )
    (net (code "25") (name "M4_BK") (class "Default")
      (node (ref "D32") (pin "1") (pinfunction "1_1") (pintype "bidirectional"))
      (node (ref "J4") (pin "8") (pinfunction "8_8") (pintype "passive"))
      (node (ref "J5") (pin "11") (pinfunction "11_11") (pintype "passive"))
    )
    (net (code "26") (name "M4_FR") (class "Default")
      (node (ref "D31") (pin "1") (pinfunction "1_1") (pintype "bidirectional"))
      (node (ref "J4") (pin "9") (pinfunction "9_9") (pintype "passive"))
      (node (ref "J5") (pin "9") (pinfunction "9_9") (pintype "passive"))
    )
    (net (code "27") (name "M4_PG") (class "Default")
      (node (ref "D34") (pin "1") (pinfunction "1_1") (pintype "bidirectional"))
      (node (ref "J4") (pin "6") (pinfunction "6_6") (pintype "passive"))
      (node (ref "J5") (pin "15") (pinfunction "15_15") (pintype "passive"))
    )
    (net (code "28") (name "M4_SV") (class "Default")
      (node (ref "D33") (pin "1") (pinfunction "1_1") (pintype "bidirectional"))
      (node (ref "J4") (pin "7") (pinfunction "7_7") (pintype "passive"))
      (node (ref "J5") (pin "13") (pinfunction "13_13") (pintype "passive"))
    )
    (net (code "29") (name "M_EN") (class "Default")
      (node (ref "D19") (pin "1") (pinfunction "1_1") (pintype "bidirectional"))
      (node (ref "J1") (pin "15") (pinfunction "9_15") (pintype "passive"))
      (node (ref "J1") (pin "7") (pinfunction "2_7") (pintype "passive"))
      (node (ref "J4") (pin "17") (pinfunction "17_17") (pintype "passive"))
      (node (ref "J4") (pin "5") (pinfunction "5_5") (pintype "passive"))
      (node (ref "J7") (pin "9") (pinfunction "9_9") (pintype "passive"))
    )
    (net (code "30") (name "Net-(C12-Pad1)") (class "Default")
      (node (ref "C12") (pin "1") (pinfunction "1_1") (pintype "passive"))
      (node (ref "R8") (pin "1") (pinfunction "1_1") (pintype "passive"))
      (node (ref "R9") (pin "2") (pinfunction "2_2") (pintype "passive"))
    )
    (net (code "31") (name "Net-(C18-Pad1)") (class "Default")
      (node (ref "C18") (pin "1") (pinfunction "1_1") (pintype "passive"))
      (node (ref "R13") (pin "1") (pinfunction "1_1") (pintype "passive"))
      (node (ref "R14") (pin "2") (pinfunction "2_2") (pintype "passive"))
    )
    (net (code "32") (name "Net-(D1-A)") (class "Default")
      (node (ref "D1") (pin "1") (pinfunction "A_1") (pintype "passive"))
      (node (ref "R12") (pin "2") (pinfunction "2_2") (pintype "passive"))
    )
    (net (code "33") (name "Net-(Q1-G)") (class "Default")
      (node (ref "Q1") (pin "1") (pinfunction "G_1") (pintype "passive"))
      (node (ref "R16") (pin "2") (pinfunction "2_2") (pintype "passive"))
      (node (ref "R17") (pin "1") (pinfunction "1_1") (pintype "passive"))
    )
    (net (code "34") (name "Net-(S1-S)") (class "Default")
      (node (ref "R16") (pin "1") (pinfunction "1_1") (pintype "passive"))
      (node (ref "S1") (pin "3") (pinfunction "S_3") (pintype "passive"))
    )
    (net (code "35") (name "Net-(U1-A0)") (class "Default")
      (node (ref "R1") (pin "2") (pinfunction "2_2") (pintype "passive"))
      (node (ref "U1") (pin "7") (pinfunction "A0_7") (pintype "bidirectional"))
    )
    (net (code "36") (name "Net-(U1-A1)") (class "Default")
      (node (ref "R2") (pin "2") (pinfunction "2_2") (pintype "passive"))
      (node (ref "U1") (pin "8") (pinfunction "A1_8") (pintype "bidirectional"))
    )
    (net (code "37") (name "Net-(U2-BOOT)") (class "Default")
      (node (ref "C9") (pin "1") (pinfunction "1_1") (pintype "passive"))
      (node (ref "U2") (pin "6") (pinfunction "BOOT_6") (pintype "bidirectional"))
    )
    (net (code "38") (name "Net-(U2-FB)") (class "Default")
      (node (ref "C12") (pin "2") (pinfunction "2_2") (pintype "passive"))
      (node (ref "R10") (pin "2") (pinfunction "2_2") (pintype "passive"))
      (node (ref "R9") (pin "1") (pinfunction "1_1") (pintype "passive"))
      (node (ref "U2") (pin "4") (pinfunction "FB_4") (pintype "bidirectional"))
    )
    (net (code "39") (name "Net-(U2-SW)") (class "Default")
      (node (ref "C9") (pin "2") (pinfunction "2_2") (pintype "passive"))
      (node (ref "L2") (pin "1") (pinfunction "1_1") (pintype "passive"))
      (node (ref "U2") (pin "2") (pinfunction "SW_2") (pintype "bidirectional"))
    )
    (net (code "40") (name "Net-(U3-BOOT)") (class "Default")
      (node (ref "C15") (pin "1") (pinfunction "1_1") (pintype "passive"))
      (node (ref "U3") (pin "6") (pinfunction "BOOT_6") (pintype "bidirectional"))
    )
    (net (code "41") (name "Net-(U3-FB)") (class "Default")
      (node (ref "C18") (pin "2") (pinfunction "2_2") (pintype "passive"))
      (node (ref "R14") (pin "1") (pinfunction "1_1") (pintype "passive"))
      (node (ref "R15") (pin "2") (pinfunction "2_2") (pintype "passive"))
      (node (ref "U3") (pin "4") (pinfunction "FB_4") (pintype "bidirectional"))
    )
    (net (code "42") (name "Net-(U3-SW)") (class "Default")
      (node (ref "C15") (pin "2") (pinfunction "2_2") (pintype "passive"))
      (node (ref "L3") (pin "1") (pinfunction "1_1") (pintype "passive"))
      (node (ref "U3") (pin "2") (pinfunction "SW_2") (pintype "bidirectional"))
    )
    (net (code "43") (name "SCL") (class "Default")
      (node (ref "D12") (pin "1") (pinfunction "1_1") (pintype "bidirectional"))
      (node (ref "J8") (pin "2") (pinfunction "2_2") (pintype "passive"))
      (node (ref "R6") (pin "1") (pinfunction "1_1") (pintype "passive"))
      (node (ref "U1") (pin "5") (pinfunction "SCL_5") (pintype "bidirectional"))
      (node (ref "X5") (pin "1") (pinfunction "S_1") (pintype "passive"))
    )
    (net (code "44") (name "SDA") (class "Default")
      (node (ref "D13") (pin "1") (pinfunction "1_1") (pintype "bidirectional"))
      (node (ref "J8") (pin "4") (pinfunction "4_4") (pintype "passive"))
      (node (ref "R7") (pin "1") (pinfunction "1_1") (pintype "passive"))
      (node (ref "U1") (pin "6") (pinfunction "SDA_6") (pintype "bidirectional"))
      (node (ref "X5") (pin "2") (pinfunction "S_2") (pintype "passive"))
    )
    (net (code "45") (name "SP1") (class "Default")
      (node (ref "D4") (pin "1") (pinfunction "1_1") (pintype "bidirectional"))
      (node (ref "J4") (pin "18") (pinfunction "18_18") (pintype "passive"))
      (node (ref "J8") (pin "10") (pinfunction "10_10") (pintype "passive"))
    )
    (net (code "46") (name "SP2") (class "Default")
      (node (ref "D36") (pin "1") (pinfunction "1_1") (pintype "bidirectional"))
      (node (ref "J4") (pin "19") (pinfunction "19_19") (pintype "passive"))
      (node (ref "J8") (pin "12") (pinfunction "12_12") (pintype "passive"))
    )
    (net (code "47") (name "SP3") (class "Default")
      (node (ref "D37") (pin "1") (pinfunction "1_1") (pintype "bidirectional"))
      (node (ref "J4") (pin "20") (pinfunction "20_20") (pintype "passive"))
      (node (ref "J8") (pin "14") (pinfunction "14_14") (pintype "passive"))
    )
    (net (code "48") (name "SP4") (class "Default")
      (node (ref "D38") (pin "1") (pinfunction "1_1") (pintype "bidirectional"))
      (node (ref "J4") (pin "21") (pinfunction "21_21") (pintype "passive"))
      (node (ref "J8") (pin "16") (pinfunction "16_16") (pintype "passive"))
    )
    (net (code "49") (name "THER_A_SCL") (class "Default")
      (node (ref "D18") (pin "1") (pinfunction "1_1") (pintype "bidirectional"))
      (node (ref "J4") (pin "2") (pinfunction "2_2") (pintype "passive"))
      (node (ref "J8") (pin "7") (pinfunction "7_7") (pintype "passive"))
    )
    (net (code "50") (name "THER_A_SDA") (class "Default")
      (node (ref "D17") (pin "1") (pinfunction "1_1") (pintype "bidirectional"))
      (node (ref "J4") (pin "1") (pinfunction "1_1") (pintype "passive"))
      (node (ref "J8") (pin "9") (pinfunction "9_9") (pintype "passive"))
    )
    (net (code "51") (name "THER_B_SCL") (class "Default")
      (node (ref "D15") (pin "1") (pinfunction "1_1") (pintype "bidirectional"))
      (node (ref "J4") (pin "4") (pinfunction "4_4") (pintype "passive"))
      (node (ref "J8") (pin "3") (pinfunction "3_3") (pintype "passive"))
    )
    (net (code "52") (name "THER_B_SDA") (class "Default")
      (node (ref "D16") (pin "1") (pinfunction "1_1") (pintype "bidirectional"))
      (node (ref "J4") (pin "3") (pinfunction "3_3") (pintype "passive"))
      (node (ref "J8") (pin "5") (pinfunction "5_5") (pintype "passive"))
    )
    (net (code "53") (name "VIN") (class "Default")
      (node (ref "C13") (pin "1") (pinfunction "1_1") (pintype "passive"))
      (node (ref "C14") (pin "1") (pinfunction "1_1") (pintype "passive"))
      (node (ref "C21") (pin "+") (pinfunction "+_+") (pintype "passive"))
      (node (ref "C7") (pin "1") (pinfunction "1_1") (pintype "passive"))
      (node (ref "C8") (pin "1") (pinfunction "1_1") (pintype "passive"))
      (node (ref "Q1") (pin "4") (pinfunction "D_4") (pintype "passive"))
      (node (ref "U2") (pin "3") (pinfunction "VIN_3") (pintype "bidirectional"))
      (node (ref "U3") (pin "3") (pinfunction "VIN_3") (pintype "bidirectional"))
    )
    (net (code "54") (name "VIN+") (class "Default")
      (node (ref "R5") (pin "2") (pinfunction "2_2") (pintype "passive"))
      (node (ref "U$9") (pin "+") (pinfunction "VCC_+") (pintype "bidirectional"))
      (node (ref "U1") (pin "1") (pinfunction "VIN+_1") (pintype "bidirectional"))
    )
    (net (code "55") (name "VIN-") (class "Default")
      (node (ref "D1") (pin "3") (pinfunction "C_3") (pintype "passive"))
      (node (ref "Q1") (pin "3") (pinfunction "S_3") (pintype "passive"))
      (node (ref "R17") (pin "2") (pinfunction "2_2") (pintype "passive"))
      (node (ref "R5") (pin "1") (pinfunction "1_1") (pintype "passive"))
      (node (ref "U1") (pin "2") (pinfunction "VIN-_2") (pintype "bidirectional"))
    )
    (net (code "56") (name "unconnected-(J1-PadMH1)") (class "Default")
      (node (ref "J1") (pin "MH1") (pinfunction "MH1_MH1") (pintype "passive"))
    )
    (net (code "57") (name "unconnected-(J1-PadMH2)") (class "Default")
      (node (ref "J1") (pin "MH2") (pinfunction "MH2_MH2") (pintype "passive"))
    )
    (net (code "58") (name "unconnected-(J4-Pad22)") (class "Default")
      (node (ref "J4") (pin "22") (pinfunction "22_22") (pintype "passive"))
    )
    (net (code "59") (name "unconnected-(J4-Pad23)") (class "Default")
      (node (ref "J4") (pin "23") (pinfunction "23_23") (pintype "passive"))
    )
    (net (code "60") (name "unconnected-(J4-Pad24)") (class "Default")
      (node (ref "J4") (pin "24") (pinfunction "24_24") (pintype "passive"))
    )
    (net (code "61") (name "unconnected-(J4-Pad25)") (class "Default")
      (node (ref "J4") (pin "25") (pinfunction "25_25") (pintype "passive"))
    )
    (net (code "62") (name "unconnected-(J5-Pad2)") (class "Default")
      (node (ref "J5") (pin "2") (pinfunction "2_2") (pintype "passive"))
    )
    (net (code "63") (name "unconnected-(J5-Pad4)") (class "Default")
      (node (ref "J5") (pin "4") (pinfunction "4_4") (pintype "passive"))
    )
    (net (code "64") (name "unconnected-(J5-Pad6)") (class "Default")
      (node (ref "J5") (pin "6") (pinfunction "6_6") (pintype "passive"))
    )
    (net (code "65") (name "unconnected-(J5-Pad8)") (class "Default")
      (node (ref "J5") (pin "8") (pinfunction "8_8") (pintype "passive"))
    )
    (net (code "66") (name "unconnected-(J5-Pad10)") (class "Default")
      (node (ref "J5") (pin "10") (pinfunction "10_10") (pintype "passive"))
    )
    (net (code "67") (name "unconnected-(J5-Pad12)") (class "Default")
      (node (ref "J5") (pin "12") (pinfunction "12_12") (pintype "passive"))
    )
    (net (code "68") (name "unconnected-(J5-Pad14)") (class "Default")
      (node (ref "J5") (pin "14") (pinfunction "14_14") (pintype "passive"))
    )
    (net (code "69") (name "unconnected-(J5-Pad16)") (class "Default")
      (node (ref "J5") (pin "16") (pinfunction "16_16") (pintype "passive"))
    )
    (net (code "70") (name "unconnected-(J6-Pad2)") (class "Default")
      (node (ref "J6") (pin "2") (pinfunction "2_2") (pintype "passive"))
    )
    (net (code "71") (name "unconnected-(J6-Pad4)") (class "Default")
      (node (ref "J6") (pin "4") (pinfunction "4_4") (pintype "passive"))
    )
    (net (code "72") (name "unconnected-(J6-Pad5)") (class "Default")
      (node (ref "J6") (pin "5") (pinfunction "5_5") (pintype "passive"))
    )
    (net (code "73") (name "unconnected-(J6-Pad6)") (class "Default")
      (node (ref "J6") (pin "6") (pinfunction "6_6") (pintype "passive"))
    )
    (net (code "74") (name "unconnected-(J6-Pad7)") (class "Default")
      (node (ref "J6") (pin "7") (pinfunction "7_7") (pintype "passive"))
    )
    (net (code "75") (name "unconnected-(J6-Pad8)") (class "Default")
      (node (ref "J6") (pin "8") (pinfunction "8_8") (pintype "passive"))
    )
    (net (code "76") (name "unconnected-(J6-Pad10)") (class "Default")
      (node (ref "J6") (pin "10") (pinfunction "10_10") (pintype "passive"))
    )
    (net (code "77") (name "unconnected-(J6-Pad12)") (class "Default")
      (node (ref "J6") (pin "12") (pinfunction "12_12") (pintype "passive"))
    )
    (net (code "78") (name "unconnected-(J6-Pad14)") (class "Default")
      (node (ref "J6") (pin "14") (pinfunction "14_14") (pintype "passive"))
    )
    (net (code "79") (name "unconnected-(J6-Pad16)") (class "Default")
      (node (ref "J6") (pin "16") (pinfunction "16_16") (pintype "passive"))
    )
    (net (code "80") (name "unconnected-(J7-Pad11)") (class "Default")
      (node (ref "J7") (pin "11") (pinfunction "11_11") (pintype "passive"))
    )
    (net (code "81") (name "unconnected-(J8-Pad6)") (class "Default")
      (node (ref "J8") (pin "6") (pinfunction "6_6") (pintype "passive"))
    )
    (net (code "82") (name "unconnected-(J8-Pad8)") (class "Default")
      (node (ref "J8") (pin "8") (pinfunction "8_8") (pintype "passive"))
    )
    (net (code "83") (name "unconnected-(PAD1-P-Pad1)") (class "Default")
      (node (ref "PAD1") (pin "1") (pinfunction "P_1") (pintype "passive"))
    )
    (net (code "84") (name "unconnected-(PAD2-P-Pad1)") (class "Default")
      (node (ref "PAD2") (pin "1") (pinfunction "P_1") (pintype "passive"))
    )
    (net (code "85") (name "unconnected-(PAD3-P-Pad1)") (class "Default")
      (node (ref "PAD3") (pin "1") (pinfunction "P_1") (pintype "passive"))
    )
    (net (code "86") (name "unconnected-(PAD4-P-Pad1)") (class "Default")
      (node (ref "PAD4") (pin "1") (pinfunction "P_1") (pintype "passive"))
    )
    (net (code "87") (name "unconnected-(PAD5-P-Pad1)") (class "Default")
      (node (ref "PAD5") (pin "1") (pinfunction "P_1") (pintype "passive"))
    )
    (net (code "88") (name "unconnected-(PAD6-P-Pad1)") (class "Default")
      (node (ref "PAD6") (pin "1") (pinfunction "P_1") (pintype "passive"))
    )
    (net (code "89") (name "unconnected-(PAD7-P-Pad1)") (class "Default")
      (node (ref "PAD7") (pin "1") (pinfunction "P_1") (pintype "passive"))
    )
    (net (code "90") (name "unconnected-(PAD8-P-Pad1)") (class "Default")
      (node (ref "PAD8") (pin "1") (pinfunction "P_1") (pintype "passive"))
    )
    (net (code "91") (name "unconnected-(PAD9-P-Pad1)") (class "Default")
      (node (ref "PAD9") (pin "1") (pinfunction "P_1") (pintype "passive"))
    )
    (net (code "92") (name "unconnected-(PAD10-P-Pad1)") (class "Default")
      (node (ref "PAD10") (pin "1") (pinfunction "P_1") (pintype "passive"))
    )
    (net (code "93") (name "unconnected-(PAD11-P-Pad1)") (class "Default")
      (node (ref "PAD11") (pin "1") (pinfunction "P_1") (pintype "passive"))
    )
    (net (code "94") (name "unconnected-(PAD12-P-Pad1)") (class "Default")
      (node (ref "PAD12") (pin "1") (pinfunction "P_1") (pintype "passive"))
    )
    (net (code "95") (name "unconnected-(PAD13-P-Pad1)") (class "Default")
      (node (ref "PAD13") (pin "1") (pinfunction "P_1") (pintype "passive"))
    )
    (net (code "96") (name "unconnected-(PAD14-P-Pad1)") (class "Default")
      (node (ref "PAD14") (pin "1") (pinfunction "P_1") (pintype "passive"))
    )
    (net (code "97") (name "unconnected-(PAD15-P-Pad1)") (class "Default")
      (node (ref "PAD15") (pin "1") (pinfunction "P_1") (pintype "passive"))
    )
    (net (code "98") (name "unconnected-(PAD16-P-Pad1)") (class "Default")
      (node (ref "PAD16") (pin "1") (pinfunction "P_1") (pintype "passive"))
    )
    (net (code "99") (name "unconnected-(PAD17-P-Pad1)") (class "Default")
      (node (ref "PAD17") (pin "1") (pinfunction "P_1") (pintype "passive"))
    )
    (net (code "100") (name "unconnected-(PAD18-P-Pad1)") (class "Default")
      (node (ref "PAD18") (pin "1") (pinfunction "P_1") (pintype "passive"))
    )
    (net (code "101") (name "unconnected-(PAD19-P-Pad1)") (class "Default")
      (node (ref "PAD19") (pin "1") (pinfunction "P_1") (pintype "passive"))
    )
    (net (code "102") (name "unconnected-(PAD20-P-Pad1)") (class "Default")
      (node (ref "PAD20") (pin "1") (pinfunction "P_1") (pintype "passive"))
    )
    (net (code "103") (name "unconnected-(PAD21-P-Pad1)") (class "Default")
      (node (ref "PAD21") (pin "1") (pinfunction "P_1") (pintype "passive"))
    )
    (net (code "104") (name "unconnected-(PAD22-P-Pad1)") (class "Default")
      (node (ref "PAD22") (pin "1") (pinfunction "P_1") (pintype "passive"))
    )
    (net (code "105") (name "unconnected-(PAD23-P-Pad1)") (class "Default")
      (node (ref "PAD23") (pin "1") (pinfunction "P_1") (pintype "passive"))
    )
    (net (code "106") (name "unconnected-(PAD24-P-Pad1)") (class "Default")
      (node (ref "PAD24") (pin "1") (pinfunction "P_1") (pintype "passive"))
    )
    (net (code "107") (name "unconnected-(PAD25-P-Pad1)") (class "Default")
      (node (ref "PAD25") (pin "1") (pinfunction "P_1") (pintype "passive"))
    )
    (net (code "108") (name "unconnected-(PAD26-P-Pad1)") (class "Default")
      (node (ref "PAD26") (pin "1") (pinfunction "P_1") (pintype "passive"))
    )
    (net (code "109") (name "unconnected-(PAD27-P-Pad1)") (class "Default")
      (node (ref "PAD27") (pin "1") (pinfunction "P_1") (pintype "passive"))
    )
    (net (code "110") (name "unconnected-(PAD28-P-Pad1)") (class "Default")
      (node (ref "PAD28") (pin "1") (pinfunction "P_1") (pintype "passive"))
    )
    (net (code "111") (name "unconnected-(PAD29-P-Pad1)") (class "Default")
      (node (ref "PAD29") (pin "1") (pinfunction "P_1") (pintype "passive"))
    )
    (net (code "112") (name "unconnected-(PAD30-P-Pad1)") (class "Default")
      (node (ref "PAD30") (pin "1") (pinfunction "P_1") (pintype "passive"))
    )
    (net (code "113") (name "unconnected-(PAD31-P-Pad1)") (class "Default")
      (node (ref "PAD31") (pin "1") (pinfunction "P_1") (pintype "passive"))
    )
    (net (code "114") (name "unconnected-(PAD32-P-Pad1)") (class "Default")
      (node (ref "PAD32") (pin "1") (pinfunction "P_1") (pintype "passive"))
    )
    (net (code "115") (name "unconnected-(PAD33-P-Pad1)") (class "Default")
      (node (ref "PAD33") (pin "1") (pinfunction "P_1") (pintype "passive"))
    )
    (net (code "116") (name "unconnected-(PAD34-P-Pad1)") (class "Default")
      (node (ref "PAD34") (pin "1") (pinfunction "P_1") (pintype "passive"))
    )
    (net (code "117") (name "unconnected-(PAD35-P-Pad1)") (class "Default")
      (node (ref "PAD35") (pin "1") (pinfunction "P_1") (pintype "passive"))
    )
    (net (code "118") (name "unconnected-(PAD36-P-Pad1)") (class "Default")
      (node (ref "PAD36") (pin "1") (pinfunction "P_1") (pintype "passive"))
    )
    (net (code "119") (name "unconnected-(PAD37-P-Pad1)") (class "Default")
      (node (ref "PAD37") (pin "1") (pinfunction "P_1") (pintype "passive"))
    )
    (net (code "120") (name "unconnected-(PAD38-P-Pad1)") (class "Default")
      (node (ref "PAD38") (pin "1") (pinfunction "P_1") (pintype "passive"))
    )
    (net (code "121") (name "unconnected-(PAD39-P-Pad1)") (class "Default")
      (node (ref "PAD39") (pin "1") (pinfunction "P_1") (pintype "passive"))
    )
    (net (code "122") (name "unconnected-(PAD41-P-Pad1)") (class "Default")
      (node (ref "PAD41") (pin "1") (pinfunction "P_1") (pintype "passive"))
    )
    (net (code "123") (name "unconnected-(PAD43-P-Pad1)") (class "Default")
      (node (ref "PAD43") (pin "1") (pinfunction "P_1") (pintype "passive"))
    )
    (net (code "124") (name "unconnected-(PAD45-P-Pad1)") (class "Default")
      (node (ref "PAD45") (pin "1") (pinfunction "P_1") (pintype "passive"))
    )
    (net (code "125") (name "unconnected-(S1-O-Pad1)") (class "Default")
      (node (ref "S1") (pin "1") (pinfunction "O_1") (pintype "passive"))
    )
  )
)
